# dual_power.net
KiCad netlist of a schematic drawn in EAGLE
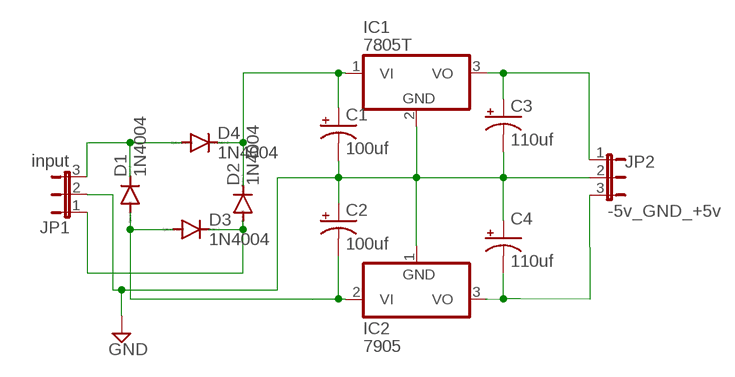
[diagram p0: schematic, sheet 1]

(export (version "E")
  (design (tool "Eeschema 10.0.6"))
  (components
    (comp (ref "C1")
      (value "100uf")
      (footprint "eagle-import:085CS_1AR")
      (libsource (lib "eagle-import") (part "CPOL-US085CS-1AR"))
    )
    (comp (ref "C2")
      (value "100uf")
      (footprint "eagle-import:085CS_1AR")
      (libsource (lib "eagle-import") (part "CPOL-US085CS-1AR"))
    )
    (comp (ref "C3")
      (value "110uf")
      (footprint "eagle-import:085CS_1AR")
      (libsource (lib "eagle-import") (part "CPOL-US085CS-1AR"))
    )
    (comp (ref "C4")
      (value "110uf")
      (footprint "eagle-import:085CS_1AR")
      (libsource (lib "eagle-import") (part "CPOL-US085CS-1AR"))
    )
    (comp (ref "D1")
      (value "1N4004")
      (footprint "eagle-import:DO41-10")
      (libsource (lib "eagle-import") (part "1N4004"))
    )
    (comp (ref "D2")
      (value "1N4004")
      (footprint "eagle-import:DO41-10")
      (libsource (lib "eagle-import") (part "1N4004"))
    )
    (comp (ref "D3")
      (value "1N4004")
      (footprint "eagle-import:DO41-10")
      (libsource (lib "eagle-import") (part "1N4004"))
    )
    (comp (ref "D4")
      (value "1N4004")
      (footprint "eagle-import:DO41-10")
      (libsource (lib "eagle-import") (part "1N4004"))
    )
    (comp (ref "IC1")
      (value "7805T")
      (footprint "eagle-import:TO220H")
      (libsource (lib "eagle-import") (part "78T05"))
    )
    (comp (ref "IC2")
      (value "7905")
      (footprint "eagle-import:TO220H")
      (libsource (lib "eagle-import") (part "79T06"))
    )
    (comp (ref "JP1")
      (value "input")
      (footprint "eagle-import:JP2")
      (libsource (lib "eagle-import") (part "JP2E"))
    )
    (comp (ref "JP2")
      (value "-5v_GND_+5v")
      (footprint "eagle-import:JP2")
      (libsource (lib "eagle-import") (part "JP2E"))
    )
  )
  (nets
    (net (code "1") (name "GND") (class "Default")
      (node (ref "C1") (pin "-") (pinfunction "-_-") (pintype "passive"))
      (node (ref "C2") (pin "+") (pinfunction "+_+") (pintype "passive"))
      (node (ref "C3") (pin "-") (pinfunction "-_-") (pintype "passive"))
      (node (ref "C4") (pin "+") (pinfunction "+_+") (pintype "passive"))
      (node (ref "IC1") (pin "2") (pinfunction "GND_2") (pintype "passive"))
      (node (ref "IC2") (pin "1") (pinfunction "GND_1") (pintype "passive"))
      (node (ref "JP1") (pin "2") (pinfunction "2_2") (pintype "passive"))
      (node (ref "JP2") (pin "2") (pinfunction "2_2") (pintype "passive"))
    )
    (net (code "2") (name "Net-(D1-PadC)") (class "Default")
      (node (ref "D1") (pin "C") (pinfunction "C_C") (pintype "passive"))
      (node (ref "D4") (pin "A") (pinfunction "A_A") (pintype "passive"))
      (node (ref "JP1") (pin "3") (pinfunction "3_3") (pintype "passive"))
    )
    (net (code "3") (name "Net-(D2-PadA)") (class "Default")
      (node (ref "D2") (pin "A") (pinfunction "A_A") (pintype "passive"))
      (node (ref "D3") (pin "C") (pinfunction "C_C") (pintype "passive"))
      (node (ref "JP1") (pin "1") (pinfunction "1_1") (pintype "passive"))
    )
    (net (code "4") (name "Net-(IC1-VI)") (class "Default")
      (node (ref "C1") (pin "+") (pinfunction "+_+") (pintype "passive"))
      (node (ref "D2") (pin "C") (pinfunction "C_C") (pintype "passive"))
      (node (ref "D4") (pin "C") (pinfunction "C_C") (pintype "passive"))
      (node (ref "IC1") (pin "1") (pinfunction "VI_1") (pintype "input"))
    )
    (net (code "5") (name "Net-(IC1-VO)") (class "Default")
      (node (ref "C3") (pin "+") (pinfunction "+_+") (pintype "passive"))
      (node (ref "IC1") (pin "3") (pinfunction "VO_3") (pintype "passive"))
      (node (ref "JP2") (pin "1") (pinfunction "1_1") (pintype "passive"))
    )
    (net (code "6") (name "Net-(IC2-VI)") (class "Default")
      (node (ref "C2") (pin "-") (pinfunction "-_-") (pintype "passive"))
      (node (ref "D1") (pin "A") (pinfunction "A_A") (pintype "passive"))
      (node (ref "D3") (pin "A") (pinfunction "A_A") (pintype "passive"))
      (node (ref "IC2") (pin "2") (pinfunction "VI_2") (pintype "input"))
    )
    (net (code "7") (name "Net-(IC2-VO)") (class "Default")
      (node (ref "C4") (pin "-") (pinfunction "-_-") (pintype "passive"))
      (node (ref "IC2") (pin "3") (pinfunction "VO_3") (pintype "passive"))
      (node (ref "JP2") (pin "3") (pinfunction "3_3") (pintype "passive"))
    )
  )
)
